# PIC18LF25K50_PINOUT.net
KiCad netlist of a schematic drawn in Altium Designer
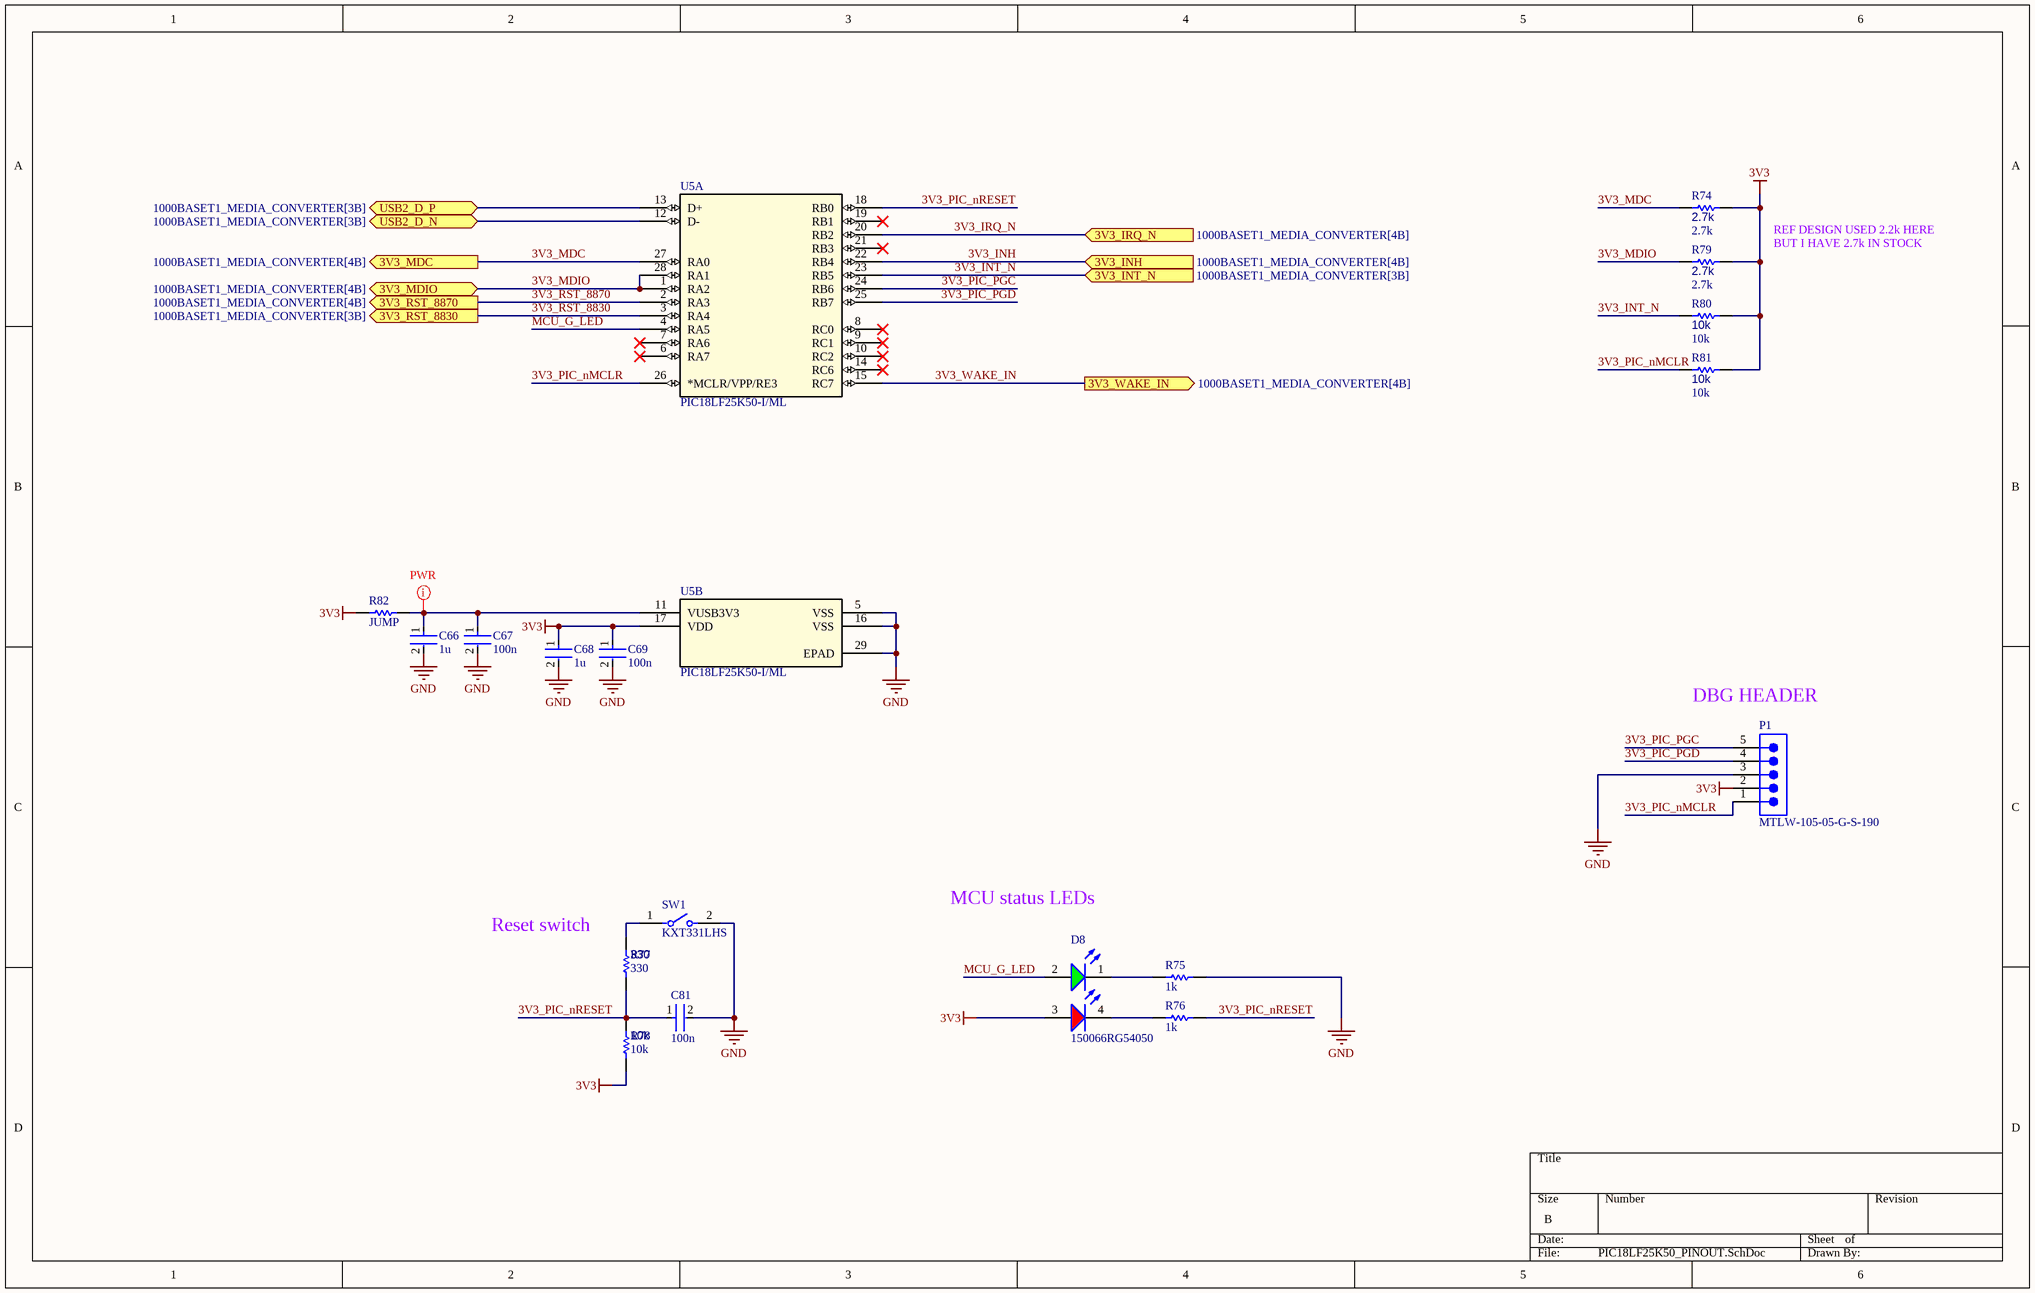
[diagram p0: PIC18LF25K50_PINOUT.SchDoc]

(export (version "E")
  (design (tool "Eeschema 10.0.6"))
  (components
    (comp (ref "C66")
      (value "1u")
      (footprint "FP-0402-L_1_0_0_05-W_0_5-IPC_A")
      (description "LARGE PADS, 0402 CAP, CHANGE COMMENT TO MATCH REAL P/N")
      (libsource (lib "Space Concordia") (part "b4654b650e69147ec39a6b967a45e02"))
    )
    (comp (ref "C67")
      (value "100n")
      (footprint "FP-0402-L_1_0_0_05-W_0_5-IPC_A")
      (description "LARGE PADS, 0402 CAP, CHANGE COMMENT TO MATCH REAL P/N")
      (libsource (lib "Space Concordia") (part "b4654b650e69147ec39a6b967a45e02"))
    )
    (comp (ref "C68")
      (value "1u")
      (footprint "FP-0402-L_1_0_0_05-W_0_5-IPC_A")
      (description "LARGE PADS, 0402 CAP, CHANGE COMMENT TO MATCH REAL P/N")
      (libsource (lib "Space Concordia") (part "b4654b650e69147ec39a6b967a45e02"))
    )
    (comp (ref "C69")
      (value "100n")
      (footprint "FP-0402-L_1_0_0_05-W_0_5-IPC_A")
      (description "LARGE PADS, 0402 CAP, CHANGE COMMENT TO MATCH REAL P/N")
      (libsource (lib "Space Concordia") (part "b4654b650e69147ec39a6b967a45e02"))
    )
    (comp (ref "C81")
      (value "100n")
      (footprint "FP-0402-L_1_0_0_05-W_0_5-IPC_A")
      (description "LARGE PADS, 0402 CAP, CHANGE COMMENT TO MATCH REAL P/N")
      (libsource (lib "Space Concordia") (part "b4654b650e69147ec39a6b967a45e02"))
    )
    (comp (ref "D8")
      (value "150066RG54050")
      (footprint "WL-SBCD_0606")
      (description "Led, Red/Grn, 180Mcd/230Mcd, 624Nm/525Nm Rohs Compliant: Yes")
      (fields (field (name "SOURCE") "rgled.SchLib"))
      (libsource (lib "Space Concordia") (part "CMP-004-00034-2"))
    )
    (comp (ref "P1")
      (value "MTLW-105-05-G-S-190")
      (footprint "SMTC-MTLW-105-05-X-S-190")
      (fields (field (name "MANUFACTURER") "Samtec"))
      (libsource (lib "Altium Content Vault") (part "SMTC-MTLW-105-05-X-S-190"))
    )
    (comp (ref "R74")
      (value "2.7k")
      (footprint "R0603B")
      (description "Resistor")
      (fields (field (name "ALTIUM_VALUE") "2.7k"))
      (libsource (lib "Space Concordia") (part "Resistor"))
    )
    (comp (ref "R75")
      (value "1k")
      (footprint "R0603B")
      (description "Resistor")
      (libsource (lib "Space Concordia") (part "Resistor"))
    )
    (comp (ref "R76")
      (value "1k")
      (footprint "R0603B")
      (description "Resistor")
      (libsource (lib "Space Concordia") (part "Resistor"))
    )
    (comp (ref "R77")
      (value "330")
      (footprint "R0603B")
      (description "Resistor")
      (fields (field (name "ALTIUM_VALUE") "330"))
      (libsource (lib "Space Concordia") (part "Resistor"))
    )
    (comp (ref "R78")
      (value "10k")
      (footprint "R0603B")
      (description "Resistor")
      (fields (field (name "ALTIUM_VALUE") "10k"))
      (libsource (lib "Space Concordia") (part "Resistor"))
    )
    (comp (ref "R79")
      (value "2.7k")
      (footprint "R0603B")
      (description "Resistor")
      (fields (field (name "ALTIUM_VALUE") "2.7k"))
      (libsource (lib "Space Concordia") (part "Resistor"))
    )
    (comp (ref "R80")
      (value "10k")
      (footprint "R0603B")
      (description "Resistor")
      (fields (field (name "ALTIUM_VALUE") "10k"))
      (libsource (lib "Space Concordia") (part "Resistor"))
    )
    (comp (ref "R81")
      (value "10k")
      (footprint "R0603B")
      (description "Resistor")
      (fields (field (name "ALTIUM_VALUE") "10k"))
      (libsource (lib "Space Concordia") (part "Resistor"))
    )
    (comp (ref "R82")
      (value "JUMP")
      (footprint "R0603B")
      (description "Resistor")
      (libsource (lib "Space Concordia") (part "Resistor"))
    )
    (comp (ref "SW1")
      (value "KXT331LHS")
      (footprint "FP-KXT331LHS-MFG")
      (description "SWITCH TACTILE SPST-NO 0.02A 15V")
      (libsource (lib "Altium Content Vault") (part "bb27bde45df87f1f469753f287ef5ae"))
    )
    (comp (ref "U5")
      (value "PIC18LF25K50-I/ML")
      (footprint "QFN65P600X600X100_HS-29N")
      (description "MCU 8-bit PIC18 PIC RISC 32KB Flash 2.5V/3.3V 28-Pin QFN EP Tube - Rail/Tube")
      (libsource (lib "Space Concordia") (part "PIC18LF25K50-I_ML"))
    )
  )
  (nets
    (net (code "1") (name "/3V3_INH") (class "Default")
      (node (ref "U5") (pin "22") (pinfunction "RB4_22") (pintype "bidirectional"))
    )
    (net (code "2") (name "/3V3_INT_N") (class "Default")
      (node (ref "R80") (pin "1") (pinfunction "1_1") (pintype "passive"))
      (node (ref "U5") (pin "23") (pinfunction "RB5_23") (pintype "bidirectional"))
    )
    (net (code "3") (name "/3V3_IRQ_N") (class "Default")
      (node (ref "U5") (pin "20") (pinfunction "RB2_20") (pintype "bidirectional"))
    )
    (net (code "4") (name "/3V3_MDC") (class "Default")
      (node (ref "R74") (pin "2") (pinfunction "2_2") (pintype "passive"))
      (node (ref "U5") (pin "27") (pinfunction "RA0_27") (pintype "bidirectional"))
    )
    (net (code "5") (name "/3V3_MDIO") (class "Default")
      (node (ref "R79") (pin "1") (pinfunction "1_1") (pintype "passive"))
      (node (ref "U5") (pin "1") (pinfunction "RA2_1") (pintype "bidirectional"))
      (node (ref "U5") (pin "28") (pinfunction "RA1_28") (pintype "bidirectional"))
    )
    (net (code "6") (name "/3V3_PIC_PGC") (class "Default")
      (node (ref "P1") (pin "5") (pinfunction "5_5") (pintype "passive"))
      (node (ref "U5") (pin "24") (pinfunction "RB6_24") (pintype "bidirectional"))
    )
    (net (code "7") (name "/3V3_PIC_PGD") (class "Default")
      (node (ref "P1") (pin "4") (pinfunction "4_4") (pintype "passive"))
      (node (ref "U5") (pin "25") (pinfunction "RB7_25") (pintype "bidirectional"))
    )
    (net (code "8") (name "/3V3_PIC_nMCLR") (class "Default")
      (node (ref "P1") (pin "1") (pinfunction "1_1") (pintype "passive"))
      (node (ref "R81") (pin "1") (pinfunction "1_1") (pintype "passive"))
      (node (ref "U5") (pin "26") (pinfunction "*MCLR/VPP/RE3_26") (pintype "bidirectional"))
    )
    (net (code "9") (name "/3V3_PIC_nRESET") (class "Default")
      (node (ref "C81") (pin "1") (pinfunction "1_1") (pintype "passive"))
      (node (ref "R76") (pin "1") (pinfunction "1_1") (pintype "passive"))
      (node (ref "R77") (pin "1") (pinfunction "1_1") (pintype "passive"))
      (node (ref "R78") (pin "2") (pinfunction "2_2") (pintype "passive"))
      (node (ref "U5") (pin "18") (pinfunction "RB0_18") (pintype "bidirectional"))
    )
    (net (code "10") (name "/3V3_RST_8830") (class "Default")
      (node (ref "U5") (pin "3") (pinfunction "RA4_3") (pintype "bidirectional"))
    )
    (net (code "11") (name "/3V3_RST_8870") (class "Default")
      (node (ref "U5") (pin "2") (pinfunction "RA3_2") (pintype "bidirectional"))
    )
    (net (code "12") (name "/3V3_WAKE_IN") (class "Default")
      (node (ref "U5") (pin "15") (pinfunction "RC7_15") (pintype "bidirectional"))
    )
    (net (code "13") (name "/MCU_G_LED") (class "Default")
      (node (ref "D8") (pin "2") (pinfunction "A_2") (pintype "passive"))
      (node (ref "U5") (pin "4") (pinfunction "RA5_4") (pintype "bidirectional"))
    )
    (net (code "14") (name "/USB2_D_N") (class "Default")
      (node (ref "U5") (pin "12") (pinfunction "D-_12") (pintype "bidirectional"))
    )
    (net (code "15") (name "/USB2_D_P") (class "Default")
      (node (ref "U5") (pin "13") (pinfunction "D+_13") (pintype "bidirectional"))
    )
    (net (code "16") (name "3V3") (class "Default")
      (node (ref "C68") (pin "1") (pinfunction "1_1") (pintype "passive"))
      (node (ref "C69") (pin "1") (pinfunction "1_1") (pintype "passive"))
      (node (ref "D8") (pin "3") (pinfunction "A_3") (pintype "passive"))
      (node (ref "P1") (pin "2") (pinfunction "2_2") (pintype "passive"))
      (node (ref "R74") (pin "1") (pinfunction "1_1") (pintype "passive"))
      (node (ref "R78") (pin "1") (pinfunction "1_1") (pintype "passive"))
      (node (ref "R79") (pin "2") (pinfunction "2_2") (pintype "passive"))
      (node (ref "R80") (pin "2") (pinfunction "2_2") (pintype "passive"))
      (node (ref "R81") (pin "2") (pinfunction "2_2") (pintype "passive"))
      (node (ref "R82") (pin "1") (pinfunction "1_1") (pintype "passive"))
      (node (ref "U5") (pin "17") (pinfunction "VDD_17") (pintype "power_in"))
    )
    (net (code "17") (name "GND") (class "Default")
      (node (ref "C66") (pin "2") (pinfunction "2_2") (pintype "passive"))
      (node (ref "C67") (pin "2") (pinfunction "2_2") (pintype "passive"))
      (node (ref "C68") (pin "2") (pinfunction "2_2") (pintype "passive"))
      (node (ref "C69") (pin "2") (pinfunction "2_2") (pintype "passive"))
      (node (ref "C81") (pin "2") (pinfunction "2_2") (pintype "passive"))
      (node (ref "P1") (pin "3") (pinfunction "3_3") (pintype "passive"))
      (node (ref "R75") (pin "1") (pinfunction "1_1") (pintype "passive"))
      (node (ref "SW1") (pin "2") (pinfunction "2_2") (pintype "passive"))
      (node (ref "U5") (pin "16") (pinfunction "VSS_16") (pintype "power_in"))
      (node (ref "U5") (pin "29") (pinfunction "EPAD_29") (pintype "passive"))
      (node (ref "U5") (pin "5") (pinfunction "VSS_5") (pintype "power_in"))
    )
    (net (code "18") (name "Net-(D8-K-Pad1)") (class "Default")
      (node (ref "D8") (pin "1") (pinfunction "K_1") (pintype "passive"))
      (node (ref "R75") (pin "2") (pinfunction "2_2") (pintype "passive"))
    )
    (net (code "19") (name "Net-(D8-K-Pad4)") (class "Default")
      (node (ref "D8") (pin "4") (pinfunction "K_4") (pintype "passive"))
      (node (ref "R76") (pin "2") (pinfunction "2_2") (pintype "passive"))
    )
    (net (code "20") (name "Net-(R77-Pad2)") (class "Default")
      (node (ref "R77") (pin "2") (pinfunction "2_2") (pintype "passive"))
      (node (ref "SW1") (pin "1") (pinfunction "1_1") (pintype "passive"))
    )
    (net (code "21") (name "Net-(U5B-VUSB3V3)") (class "Default")
      (node (ref "C66") (pin "1") (pinfunction "1_1") (pintype "passive"))
      (node (ref "C67") (pin "1") (pinfunction "1_1") (pintype "passive"))
      (node (ref "R82") (pin "2") (pinfunction "2_2") (pintype "passive"))
      (node (ref "U5") (pin "11") (pinfunction "VUSB3V3_11") (pintype "power_in"))
    )
    (net (code "22") (name "unconnected-(U5A-RA6-Pad7)") (class "Default")
      (node (ref "U5") (pin "7") (pinfunction "RA6_7") (pintype "bidirectional+no_connect"))
    )
    (net (code "23") (name "unconnected-(U5A-RA7-Pad6)") (class "Default")
      (node (ref "U5") (pin "6") (pinfunction "RA7_6") (pintype "bidirectional+no_connect"))
    )
    (net (code "24") (name "unconnected-(U5A-RB1-Pad19)") (class "Default")
      (node (ref "U5") (pin "19") (pinfunction "RB1_19") (pintype "bidirectional+no_connect"))
    )
    (net (code "25") (name "unconnected-(U5A-RB3-Pad21)") (class "Default")
      (node (ref "U5") (pin "21") (pinfunction "RB3_21") (pintype "bidirectional+no_connect"))
    )
    (net (code "26") (name "unconnected-(U5A-RC0-Pad8)") (class "Default")
      (node (ref "U5") (pin "8") (pinfunction "RC0_8") (pintype "bidirectional+no_connect"))
    )
    (net (code "27") (name "unconnected-(U5A-RC1-Pad9)") (class "Default")
      (node (ref "U5") (pin "9") (pinfunction "RC1_9") (pintype "bidirectional+no_connect"))
    )
    (net (code "28") (name "unconnected-(U5A-RC2-Pad10)") (class "Default")
      (node (ref "U5") (pin "10") (pinfunction "RC2_10") (pintype "bidirectional+no_connect"))
    )
    (net (code "29") (name "unconnected-(U5A-RC6-Pad14)") (class "Default")
      (node (ref "U5") (pin "14") (pinfunction "RC6_14") (pintype "bidirectional+no_connect"))
    )
  )
)
